# miniboard.net
KiCad netlist of a schematic drawn in EAGLE
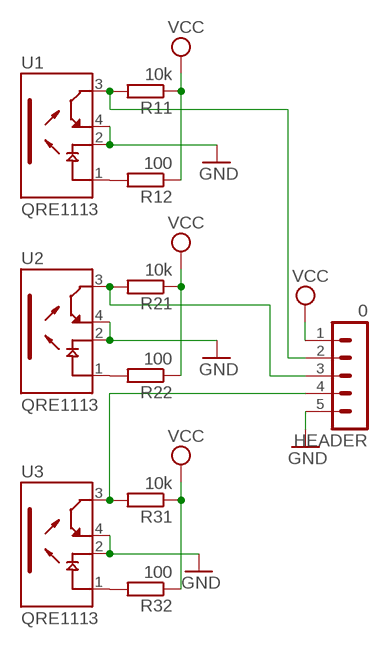
[diagram p0: schematic, sheet 1]

(export (version "E")
  (design (tool "Eeschema 10.0.6"))
  (components
    (comp (ref "HEADER")
      (value "0")
      (footprint "eagle-import:MA05-1")
      (libsource (lib "eagle-import") (part "MA05-1"))
    )
    (comp (ref "R11")
      (value "10k")
      (footprint "eagle-import:0207_10")
      (libsource (lib "eagle-import") (part "R-EU_0207/10"))
    )
    (comp (ref "R12")
      (value "100")
      (footprint "eagle-import:0207_10")
      (libsource (lib "eagle-import") (part "R-EU_0207/10"))
    )
    (comp (ref "R21")
      (value "10k")
      (footprint "eagle-import:0207_10")
      (libsource (lib "eagle-import") (part "R-EU_0207/10"))
    )
    (comp (ref "R22")
      (value "100")
      (footprint "eagle-import:0207_10")
      (libsource (lib "eagle-import") (part "R-EU_0207/10"))
    )
    (comp (ref "R31")
      (value "10k")
      (footprint "eagle-import:0207_10")
      (libsource (lib "eagle-import") (part "R-EU_0207/10"))
    )
    (comp (ref "R32")
      (value "100")
      (footprint "eagle-import:0207_10")
      (libsource (lib "eagle-import") (part "R-EU_0207/10"))
    )
    (comp (ref "U1")
      (value "QRE1113")
      (footprint "eagle-import:DIP400W50P180L360H200Q4")
      (fields (field (name "MANUFACTURER") "On Semiconductor"))
      (libsource (lib "eagle-import") (part "QRE1113"))
    )
    (comp (ref "U2")
      (value "QRE1113")
      (footprint "eagle-import:DIP400W50P180L360H200Q4")
      (fields (field (name "MANUFACTURER") "On Semiconductor"))
      (libsource (lib "eagle-import") (part "QRE1113"))
    )
    (comp (ref "U3")
      (value "QRE1113")
      (footprint "eagle-import:DIP400W50P180L360H200Q4")
      (fields (field (name "MANUFACTURER") "On Semiconductor"))
      (libsource (lib "eagle-import") (part "QRE1113"))
    )
  )
  (nets
    (net (code "1") (name "GND") (class "Default")
      (node (ref "HEADER") (pin "5") (pinfunction "5_5") (pintype "passive"))
      (node (ref "U1") (pin "2") (pinfunction "C_2") (pintype "passive"))
      (node (ref "U1") (pin "4") (pinfunction "ET_4") (pintype "passive"))
      (node (ref "U2") (pin "2") (pinfunction "C_2") (pintype "passive"))
      (node (ref "U2") (pin "4") (pinfunction "ET_4") (pintype "passive"))
      (node (ref "U3") (pin "2") (pinfunction "C_2") (pintype "passive"))
      (node (ref "U3") (pin "4") (pinfunction "ET_4") (pintype "passive"))
    )
    (net (code "2") (name "Net-(U1-A)") (class "Default")
      (node (ref "R12") (pin "2") (pinfunction "2_2") (pintype "passive"))
      (node (ref "U1") (pin "1") (pinfunction "A_1") (pintype "passive"))
    )
    (net (code "3") (name "Net-(U1-CT)") (class "Default")
      (node (ref "HEADER") (pin "2") (pinfunction "2_2") (pintype "passive"))
      (node (ref "R11") (pin "2") (pinfunction "2_2") (pintype "passive"))
      (node (ref "U1") (pin "3") (pinfunction "CT_3") (pintype "passive"))
    )
    (net (code "4") (name "Net-(U2-A)") (class "Default")
      (node (ref "R22") (pin "2") (pinfunction "2_2") (pintype "passive"))
      (node (ref "U2") (pin "1") (pinfunction "A_1") (pintype "passive"))
    )
    (net (code "5") (name "Net-(U2-CT)") (class "Default")
      (node (ref "HEADER") (pin "3") (pinfunction "3_3") (pintype "passive"))
      (node (ref "R21") (pin "2") (pinfunction "2_2") (pintype "passive"))
      (node (ref "U2") (pin "3") (pinfunction "CT_3") (pintype "passive"))
    )
    (net (code "6") (name "Net-(U3-A)") (class "Default")
      (node (ref "R32") (pin "2") (pinfunction "2_2") (pintype "passive"))
      (node (ref "U3") (pin "1") (pinfunction "A_1") (pintype "passive"))
    )
    (net (code "7") (name "Net-(U3-CT)") (class "Default")
      (node (ref "HEADER") (pin "4") (pinfunction "4_4") (pintype "passive"))
      (node (ref "R31") (pin "2") (pinfunction "2_2") (pintype "passive"))
      (node (ref "U3") (pin "3") (pinfunction "CT_3") (pintype "passive"))
    )
    (net (code "8") (name "VCC") (class "Default")
      (node (ref "HEADER") (pin "1") (pinfunction "1_1") (pintype "passive"))
      (node (ref "R11") (pin "1") (pinfunction "1_1") (pintype "passive"))
      (node (ref "R12") (pin "1") (pinfunction "1_1") (pintype "passive"))
      (node (ref "R21") (pin "1") (pinfunction "1_1") (pintype "passive"))
      (node (ref "R22") (pin "1") (pinfunction "1_1") (pintype "passive"))
      (node (ref "R31") (pin "1") (pinfunction "1_1") (pintype "passive"))
      (node (ref "R32") (pin "1") (pinfunction "1_1") (pintype "passive"))
    )
  )
)
